# SCH_LED-CHASER-chiikawa_2025-10-19.net
KiCad netlist of a schematic drawn in EasyEDA
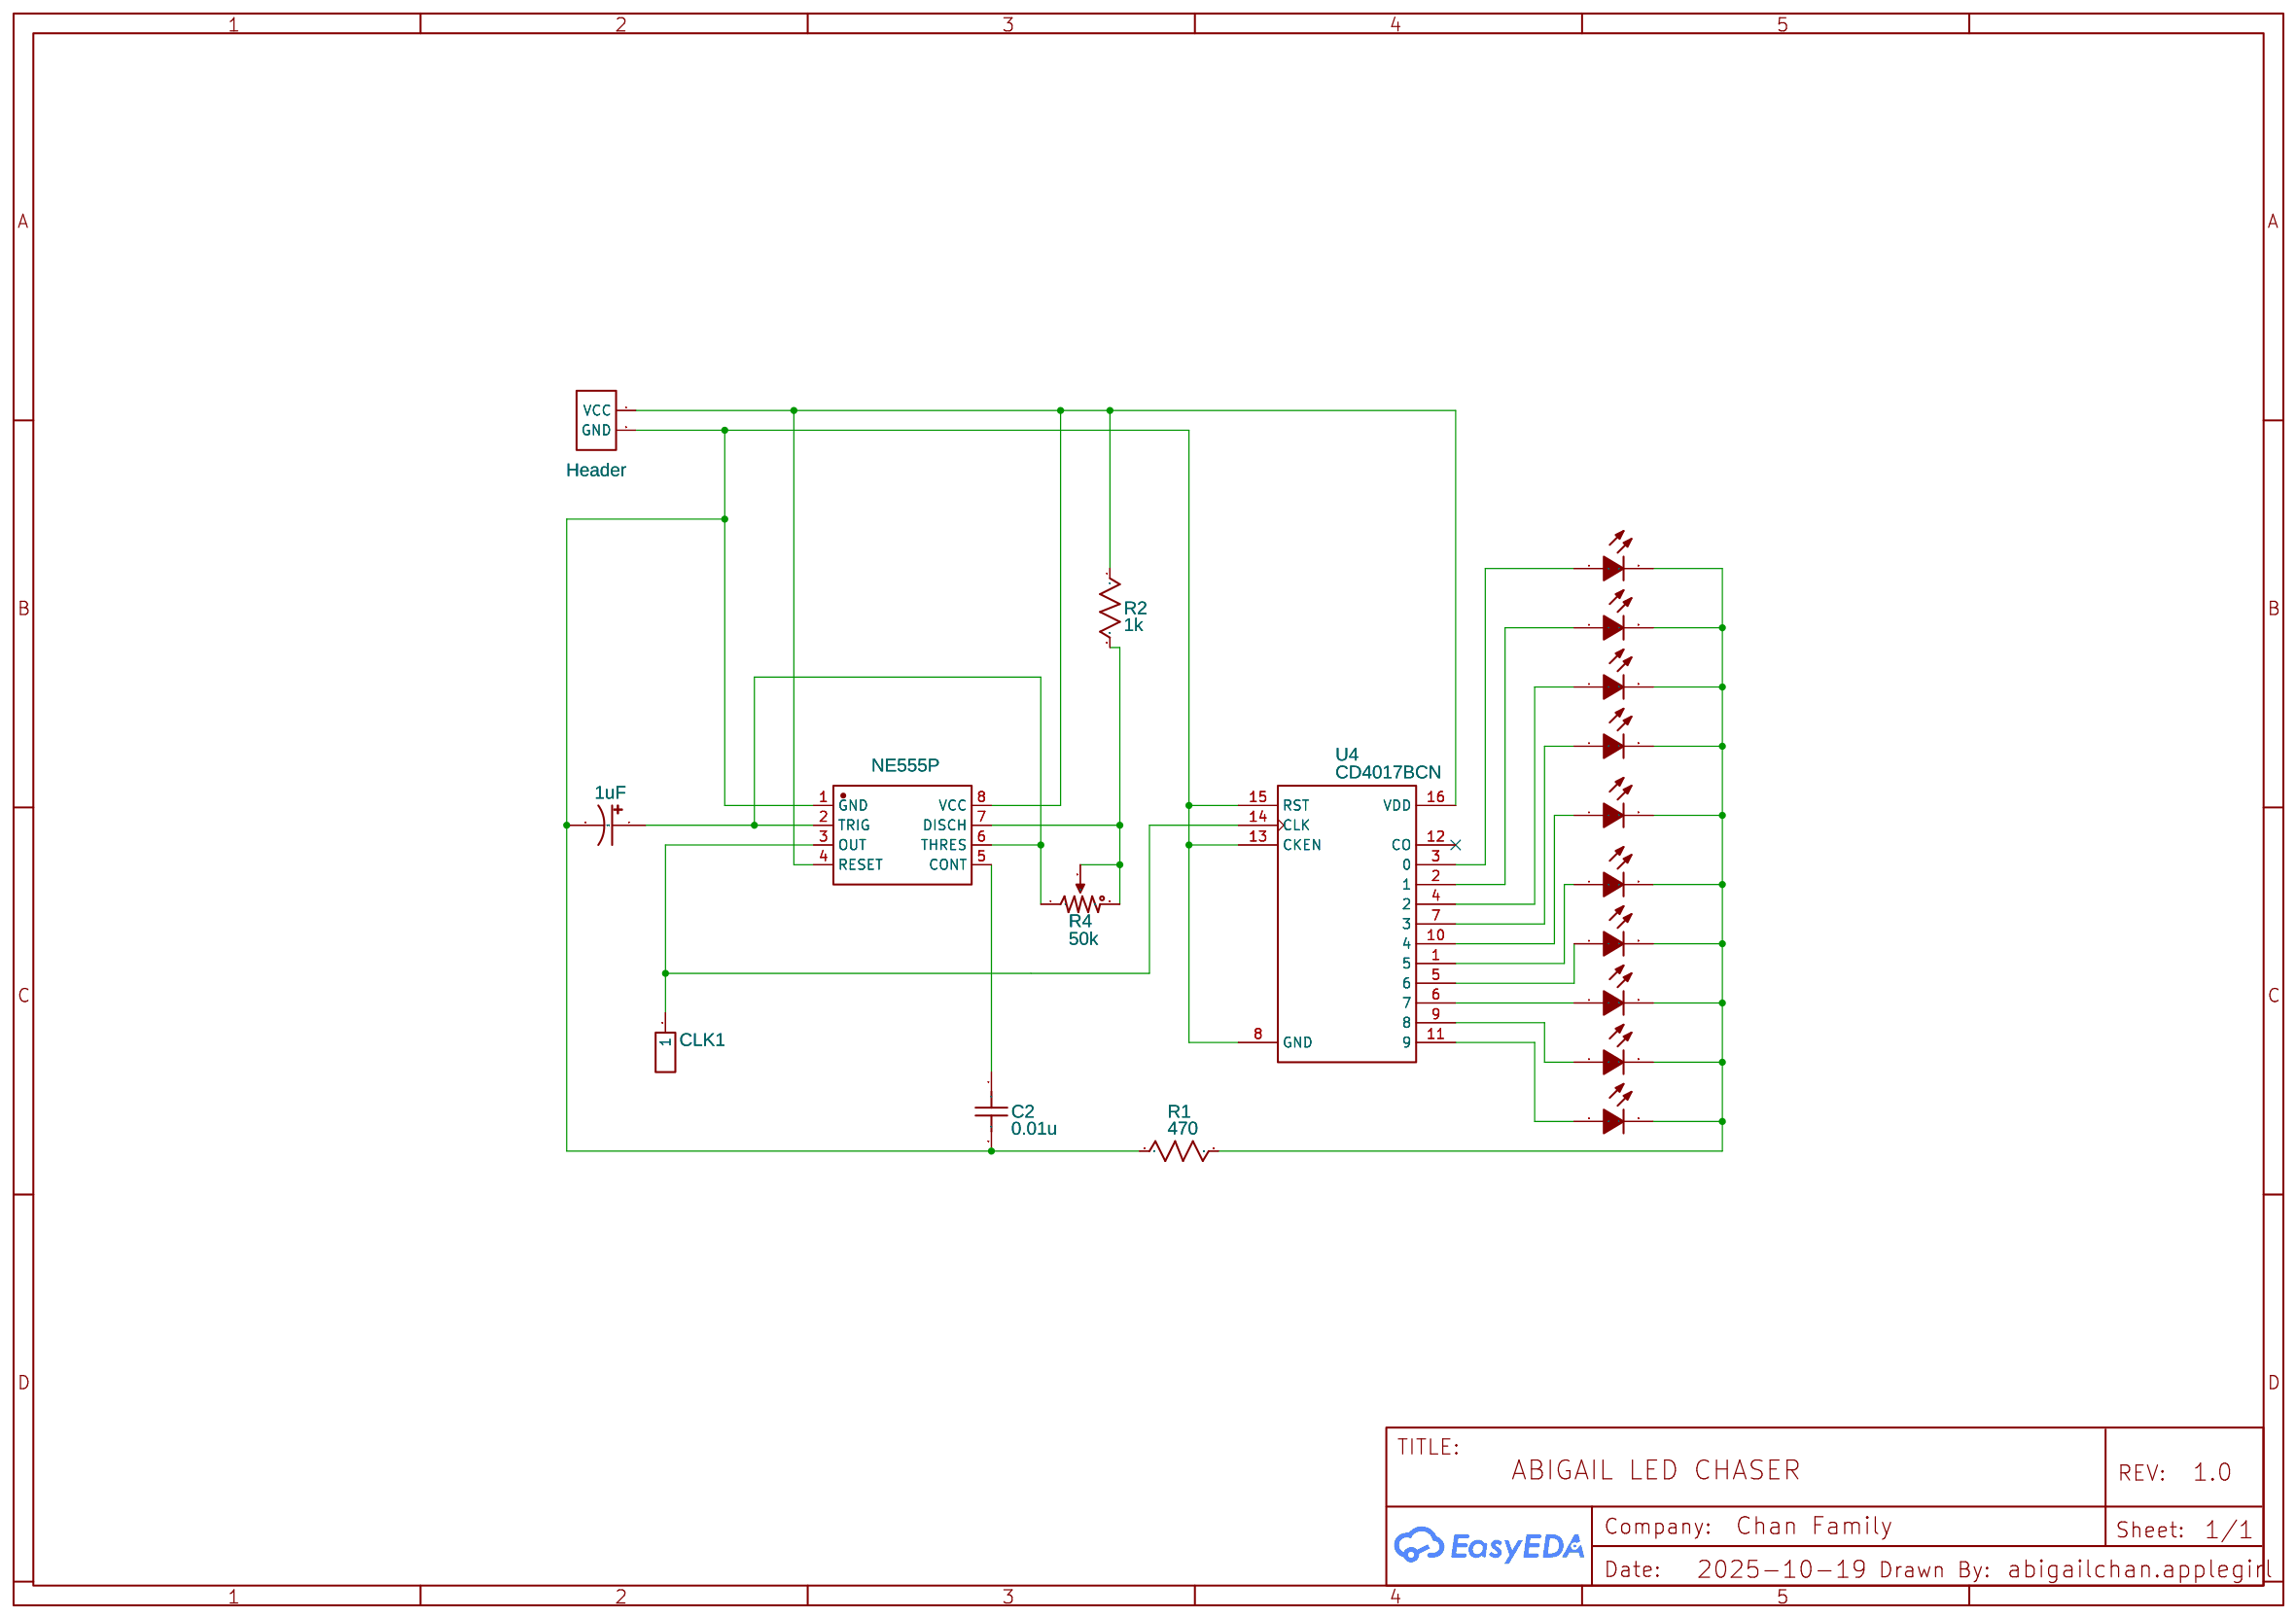
[diagram p0: schematic sheet]

(export (version "E")
  (design (tool "Eeschema 10.0.6"))
  (components
    (comp (ref "BLUE1") (value "LED_5MM") (libsource (lib "") (part "LED_5MM")))
    (comp (ref "BLUE2") (value "LED_5MM") (libsource (lib "") (part "LED_5MM")))
    (comp (ref "BLUE3") (value "LED_5MM") (libsource (lib "") (part "LED_5MM")))
    (comp (ref "BLUE4") (value "LED_5MM") (libsource (lib "") (part "LED_5MM")))
    (comp (ref "BLUE5") (value "LED_5MM") (libsource (lib "") (part "LED_5MM")))
    (comp (ref "BLUE6") (value "LED_5MM") (libsource (lib "") (part "LED_5MM")))
    (comp (ref "BLUE7") (value "LED_5MM") (libsource (lib "") (part "LED_5MM")))
    (comp (ref "BLUE8") (value "LED_5MM") (libsource (lib "") (part "LED_5MM")))
    (comp (ref "BLUE9") (value "LED_5MM") (libsource (lib "") (part "LED_5MM")))
    (comp (ref "BLUE10") (value "LED_5MM") (libsource (lib "") (part "LED_5MM")))
    (comp (ref "C1")
      (value "1uF")
      (fields (field (name "Manufacturer Part") "UVZ1H010MDD") (field (name "Manufacturer") "Nichicon(尼吉康)"))
      (libsource (lib "") (part "UVZ1H010MDD"))
    )
    (comp (ref "C2") (value "0.01u") (libsource (lib "") (part "C_0603_US")))
    (comp (ref "CLK1")
      (value "C81276")
      (fields
        (field (name "Manufacturer Part") "2.54-1*1P针")
        (field (name "Manufacturer") "BOOMELE(Boom Precision Elec)")
      )
      (libsource (lib "") (part "Header-Male-2.54_1x1"))
    )
    (comp (ref "H1") (value "Header") (libsource (lib "") (part "HEADER-FEMALE-2.54_1X2")))
    (comp (ref "R1")
      (value "470")
      (fields (field (name "Manufacturer Part") "?"))
      (libsource (lib "") (part "Resistor"))
    )
    (comp (ref "R2")
      (value "1k")
      (fields (field (name "Manufacturer Part") "?"))
      (libsource (lib "") (part "Resistor_1"))
    )
    (comp (ref "R4")
      (value "50k")
      (fields (field (name "Manufacturer Part") "?"))
      (libsource (lib "") (part "Potentiometer"))
    )
    (comp (ref "U2")
      (value "NE555P")
      (fields (field (name "Manufacturer") "TI(德州仪器)"))
      (libsource (lib "") (part "NE555P"))
    )
    (comp (ref "U4") (value "CD4017BCN") (libsource (lib "") (part "CD4017BCN")))
  )
  (nets
    (net (code "1") (name "Net-(BLUE1-A)") (class "Default")
      (node (ref "BLUE1") (pin "1") (pinfunction "A_1") (pintype "input"))
      (node (ref "U4") (pin "11") (pinfunction "9_11") (pintype "output"))
    )
    (net (code "2") (name "Net-(BLUE1-K)") (class "Default")
      (node (ref "BLUE1") (pin "2") (pinfunction "K_2") (pintype "input"))
      (node (ref "BLUE10") (pin "2") (pinfunction "K_2") (pintype "input"))
      (node (ref "BLUE2") (pin "2") (pinfunction "K_2") (pintype "input"))
      (node (ref "BLUE3") (pin "2") (pinfunction "K_2") (pintype "input"))
      (node (ref "BLUE4") (pin "2") (pinfunction "K_2") (pintype "input"))
      (node (ref "BLUE5") (pin "2") (pinfunction "K_2") (pintype "input"))
      (node (ref "BLUE6") (pin "2") (pinfunction "K_2") (pintype "input"))
      (node (ref "BLUE7") (pin "2") (pinfunction "K_2") (pintype "input"))
      (node (ref "BLUE8") (pin "2") (pinfunction "K_2") (pintype "input"))
      (node (ref "BLUE9") (pin "2") (pinfunction "K_2") (pintype "input"))
      (node (ref "R1") (pin "2") (pinfunction "2_2") (pintype "unspecified"))
    )
    (net (code "3") (name "Net-(BLUE2-A)") (class "Default")
      (node (ref "BLUE2") (pin "1") (pinfunction "A_1") (pintype "input"))
      (node (ref "U4") (pin "3") (pinfunction "0_3") (pintype "output"))
    )
    (net (code "4") (name "Net-(BLUE3-A)") (class "Default")
      (node (ref "BLUE3") (pin "1") (pinfunction "A_1") (pintype "input"))
      (node (ref "U4") (pin "2") (pinfunction "1_2") (pintype "output"))
    )
    (net (code "5") (name "Net-(BLUE4-A)") (class "Default")
      (node (ref "BLUE4") (pin "1") (pinfunction "A_1") (pintype "input"))
      (node (ref "U4") (pin "4") (pinfunction "2_4") (pintype "output"))
    )
    (net (code "6") (name "Net-(BLUE5-A)") (class "Default")
      (node (ref "BLUE5") (pin "1") (pinfunction "A_1") (pintype "input"))
      (node (ref "U4") (pin "7") (pinfunction "3_7") (pintype "output"))
    )
    (net (code "7") (name "Net-(BLUE6-A)") (class "Default")
      (node (ref "BLUE6") (pin "1") (pinfunction "A_1") (pintype "input"))
      (node (ref "U4") (pin "9") (pinfunction "8_9") (pintype "output"))
    )
    (net (code "8") (name "Net-(BLUE7-A)") (class "Default")
      (node (ref "BLUE7") (pin "1") (pinfunction "A_1") (pintype "input"))
      (node (ref "U4") (pin "6") (pinfunction "7_6") (pintype "output"))
    )
    (net (code "9") (name "Net-(BLUE8-A)") (class "Default")
      (node (ref "BLUE8") (pin "1") (pinfunction "A_1") (pintype "input"))
      (node (ref "U4") (pin "5") (pinfunction "6_5") (pintype "output"))
    )
    (net (code "10") (name "Net-(BLUE9-A)") (class "Default")
      (node (ref "BLUE9") (pin "1") (pinfunction "A_1") (pintype "input"))
      (node (ref "U4") (pin "1") (pinfunction "5_1") (pintype "output"))
    )
    (net (code "11") (name "Net-(BLUE10-A)") (class "Default")
      (node (ref "BLUE10") (pin "1") (pinfunction "A_1") (pintype "input"))
      (node (ref "U4") (pin "10") (pinfunction "4_10") (pintype "output"))
    )
    (net (code "12") (name "Net-(H1-GND)") (class "Default")
      (node (ref "C1") (pin "2") (pinfunction "2_2") (pintype "unspecified"))
      (node (ref "C2") (pin "2") (pinfunction "2_2") (pintype "unspecified"))
      (node (ref "H1") (pin "2") (pinfunction "GND_2") (pintype "unspecified"))
      (node (ref "R1") (pin "1") (pinfunction "1_1") (pintype "unspecified"))
      (node (ref "U2") (pin "1") (pinfunction "GND_1") (pintype "unspecified"))
      (node (ref "U4") (pin "13") (pinfunction "CKEN_13") (pintype "unspecified"))
      (node (ref "U4") (pin "15") (pinfunction "RST_15") (pintype "unspecified"))
      (node (ref "U4") (pin "8") (pinfunction "GND_8") (pintype "passive"))
    )
    (net (code "13") (name "Net-(H1-VCC)") (class "Default")
      (node (ref "H1") (pin "1") (pinfunction "VCC_1") (pintype "unspecified"))
      (node (ref "R2") (pin "1") (pinfunction "1_1") (pintype "unspecified"))
      (node (ref "U2") (pin "4") (pinfunction "RESET_4") (pintype "unspecified"))
      (node (ref "U2") (pin "8") (pinfunction "VCC_8") (pintype "unspecified"))
      (node (ref "U4") (pin "16") (pinfunction "VDD_16") (pintype "passive"))
    )
    (net (code "14") (name "Net-(R4-2)") (class "Default")
      (node (ref "R2") (pin "2") (pinfunction "2_2") (pintype "unspecified"))
      (node (ref "R4") (pin "2") (pinfunction "3_2") (pintype "unspecified"))
      (node (ref "R4") (pin "3") (pinfunction "2_3") (pintype "unspecified"))
      (node (ref "U2") (pin "7") (pinfunction "DISCH_7") (pintype "unspecified"))
    )
    (net (code "15") (name "Net-(U2-CONT)") (class "Default")
      (node (ref "C2") (pin "1") (pinfunction "1_1") (pintype "unspecified"))
      (node (ref "U2") (pin "5") (pinfunction "CONT_5") (pintype "unspecified"))
    )
    (net (code "16") (name "Net-(U2-OUT)") (class "Default")
      (node (ref "CLK1") (pin "1") (pinfunction "1_1") (pintype "unspecified"))
      (node (ref "U2") (pin "3") (pinfunction "OUT_3") (pintype "unspecified"))
      (node (ref "U4") (pin "14") (pinfunction "CLK_14") (pintype "unspecified"))
    )
    (net (code "17") (name "Net-(U2-THRES)") (class "Default")
      (node (ref "C1") (pin "1") (pinfunction "1_1") (pintype "unspecified"))
      (node (ref "R4") (pin "1") (pinfunction "1_1") (pintype "unspecified"))
      (node (ref "U2") (pin "2") (pinfunction "TRIG_2") (pintype "unspecified"))
      (node (ref "U2") (pin "6") (pinfunction "THRES_6") (pintype "unspecified"))
    )
    (net (code "18") (name "unconnected-(U4-CO-Pad12)") (class "Default")
      (node (ref "U4") (pin "12") (pinfunction "CO_12") (pintype "output+no_connect"))
    )
  )
)
